# 02_POWER.net
KiCad netlist of a schematic drawn in Altium Designer
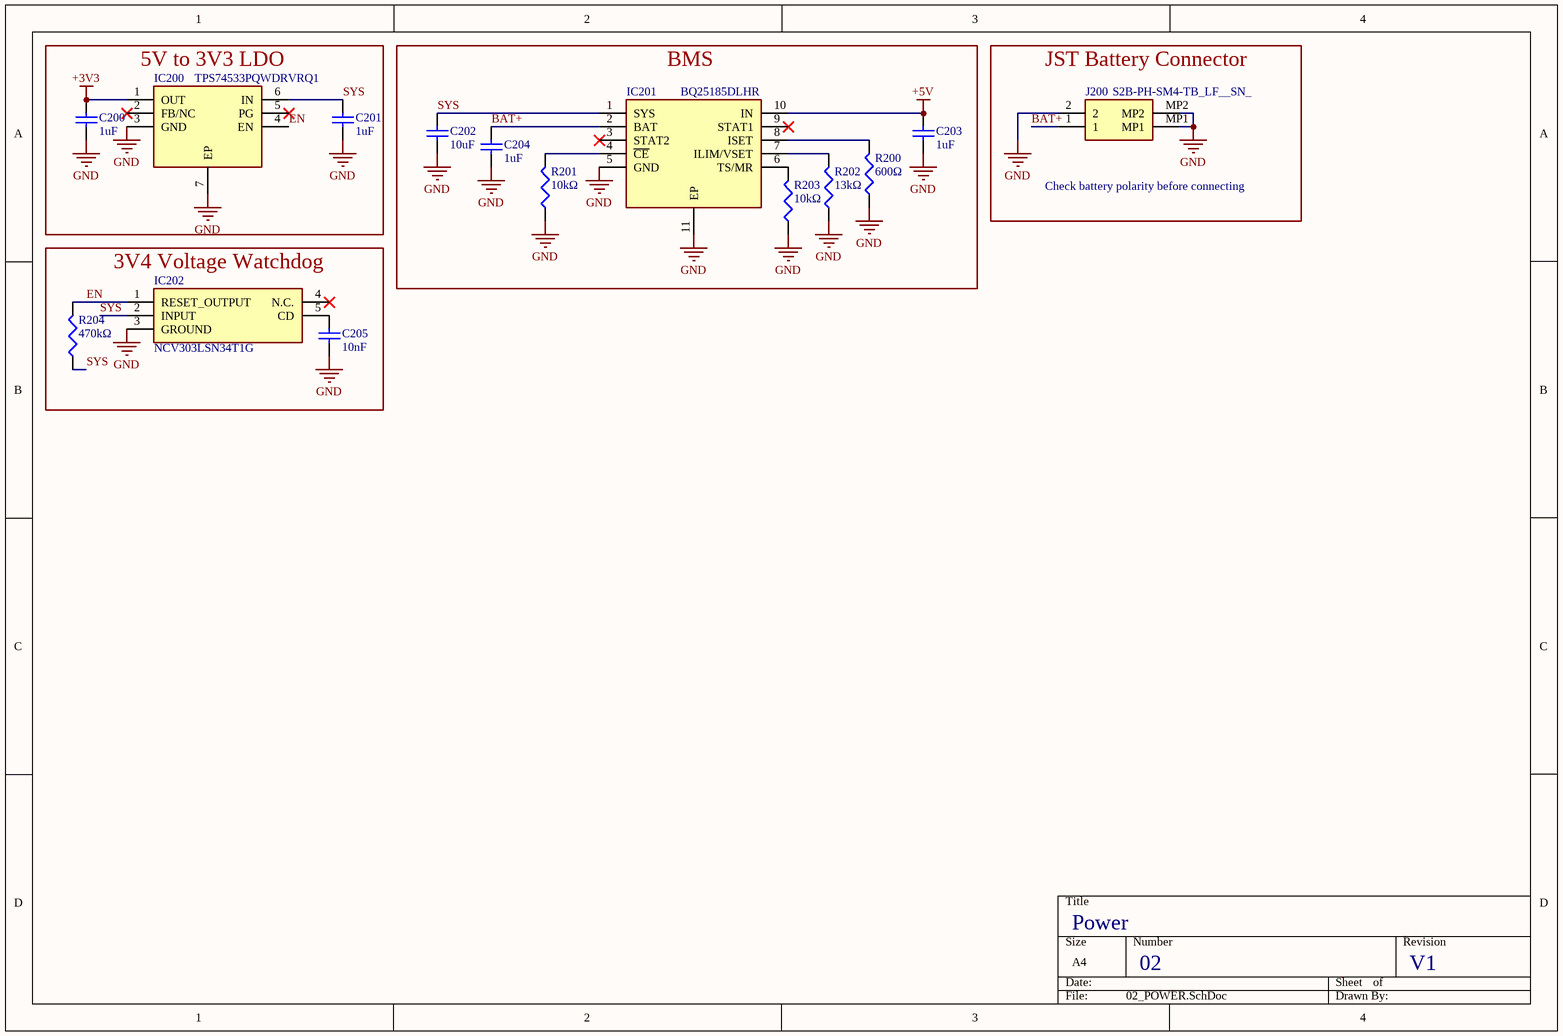
[diagram p0: 02_POWER.SchDoc]

(export (version "E")
  (design (tool "Eeschema 10.0.6"))
  (components
    (comp (ref "C200")
      (value "1uF")
      (footprint "CAPC1005X55X25LL05T10")
      (description "Chip Capacitor, 1 uF, +/- 10%, 6.3 V, 0402 (1005 Metric)")
      (fields (field (name "TOLERANCE") "10%") (field (name "Comment") "Capacitor 1 uF +/- 10% 6.3 V 0402"))
      (libsource (lib "CPRT Workspace") (part "CAP-NP-2"))
    )
    (comp (ref "C201")
      (value "1uF")
      (footprint "CAPC1005X55X25LL05T10")
      (description "Chip Capacitor, 1 uF, +/- 10%, 6.3 V, 0402 (1005 Metric)")
      (fields (field (name "TOLERANCE") "10%") (field (name "Comment") "Capacitor 1 uF +/- 10% 6.3 V 0402"))
      (libsource (lib "CPRT Workspace") (part "CAP-NP-2"))
    )
    (comp (ref "C202")
      (value "10uF")
      (footprint "CAPC1005X55X25LL05T10")
      (description "Chip Capacitor, 1 uF, +/- 10%, 6.3 V, 0402 (1005 Metric)")
      (fields (field (name "TOLERANCE") "10%") (field (name "Comment") "Capacitor 1 uF +/- 10% 6.3 V 0402"))
      (libsource (lib "CPRT Workspace") (part "CAP-NP-2"))
    )
    (comp (ref "C203")
      (value "1uF")
      (footprint "CAPC1005X55X25LL05T10")
      (description "Chip Capacitor, 1 uF, +/- 10%, 6.3 V, 0402 (1005 Metric)")
      (fields (field (name "TOLERANCE") "10%") (field (name "Comment") "Capacitor 1 uF +/- 10% 6.3 V 0402"))
      (libsource (lib "CPRT Workspace") (part "CAP-NP-2"))
    )
    (comp (ref "C204")
      (value "1uF")
      (footprint "CAPC1005X55X25LL05T10")
      (description "Chip Capacitor, 1 uF, +/- 10%, 6.3 V, 0402 (1005 Metric)")
      (fields (field (name "TOLERANCE") "10%") (field (name "Comment") "Capacitor 1 uF +/- 10% 6.3 V 0402"))
      (libsource (lib "CPRT Workspace") (part "CAP-NP-2"))
    )
    (comp (ref "C205")
      (value "10nF")
      (footprint "CAPC1005X55X25LL05T10")
      (description "Chip Capacitor, 1 uF, +/- 10%, 6.3 V, 0402 (1005 Metric)")
      (fields (field (name "TOLERANCE") "10%") (field (name "Comment") "Capacitor 1 uF +/- 10% 6.3 V 0402"))
      (libsource (lib "CPRT Workspace") (part "CAP-NP-2"))
    )
    (comp (ref "IC200")
      (value "TPS74533PQWDRVRQ1")
      (footprint "SON65P200X200X80-7N")
      (description "Integrated Circuit")
      (fields (field (name "MOUSER PART NUMBER") "595-PS74533PQWDRVRQ1"))
      (libsource (lib "Schlib1") (part "TPS74533PQWDRVRQ1"))
    )
    (comp (ref "IC201")
      (value "BQ25185DLHR")
      (footprint "SON40P220X200X80-11N")
      (description "Integrated Circuit")
      (fields (field (name "MOUSER PART NUMBER") "595-BQ25185DLHR"))
      (libsource (lib "Schlib1") (part "BQ25185DLHR"))
    )
    (comp (ref "IC202")
      (value "NCV303LSN34T1G")
      (footprint "SOT95P275X110-5N")
      (description "Integrated Circuit")
      (fields (field (name "MOUSER PART NUMBER") "863-NCV303LSN34T1G"))
      (libsource (lib "Schlib1") (part "NCV303LSN34T1G"))
    )
    (comp (ref "J200")
      (value "S2B-PH-SM4-TB_LF__SN_")
      (footprint "S2BPHSM4TBLFSN")
      (description "Connector")
      (fields (field (name "MANUFACTURER_PART_NUMBER") "S2B-PH-SM4-TB(LF)(SN)"))
      (libsource (lib "Schlib1") (part "S2B-PH-SM4-TB_LF__SN_"))
    )
    (comp (ref "R200")
      (value "600Ω")
      (footprint "RESC0402(1005)_L")
      (description "100R 0.063W 1% 0402 (1005 Metric)  SMD")
      (fields (field (name "TOLERANCE") "1%") (field (name "POWER") "63mW"))
      (libsource (lib "CPRT Workspace") (part "100R2F"))
    )
    (comp (ref "R201")
      (value "10kΩ")
      (footprint "RESC0402(1005)_L")
      (description "100R 0.063W 1% 0402 (1005 Metric)  SMD")
      (fields (field (name "TOLERANCE") "1%") (field (name "POWER") "63mW"))
      (libsource (lib "CPRT Workspace") (part "100R2F"))
    )
    (comp (ref "R202")
      (value "13kΩ")
      (footprint "RESC0402(1005)_L")
      (description "100R 0.063W 1% 0402 (1005 Metric)  SMD")
      (fields (field (name "TOLERANCE") "1%") (field (name "POWER") "63mW"))
      (libsource (lib "CPRT Workspace") (part "100R2F"))
    )
    (comp (ref "R203")
      (value "10kΩ")
      (footprint "RESC0402(1005)_L")
      (description "100R 0.063W 1% 0402 (1005 Metric)  SMD")
      (fields (field (name "TOLERANCE") "1%") (field (name "POWER") "63mW"))
      (libsource (lib "CPRT Workspace") (part "100R2F"))
    )
    (comp (ref "R204")
      (value "470kΩ")
      (footprint "RESC0402(1005)_L")
      (description "100R 0.063W 1% 0402 (1005 Metric)  SMD")
      (fields (field (name "TOLERANCE") "1%") (field (name "POWER") "63mW"))
      (libsource (lib "CPRT Workspace") (part "100R2F"))
    )
  )
  (nets
    (net (code "1") (name "+3V3") (class "Default")
      (node (ref "C200") (pin "2") (pinfunction "2_2") (pintype "passive"))
      (node (ref "IC200") (pin "1") (pinfunction "OUT_1") (pintype "passive"))
    )
    (net (code "2") (name "+5V") (class "Default")
      (node (ref "C203") (pin "2") (pinfunction "2_2") (pintype "passive"))
      (node (ref "IC201") (pin "10") (pinfunction "IN_10") (pintype "passive"))
    )
    (net (code "3") (name "/BAT+") (class "Default")
      (node (ref "C204") (pin "2") (pinfunction "2_2") (pintype "passive"))
      (node (ref "IC201") (pin "2") (pinfunction "BAT_2") (pintype "passive"))
      (node (ref "J200") (pin "1") (pinfunction "1_1") (pintype "passive"))
    )
    (net (code "4") (name "/EN") (class "Default")
      (node (ref "IC200") (pin "4") (pinfunction "EN_4") (pintype "passive"))
      (node (ref "IC202") (pin "1") (pinfunction "RESET_OUTPUT_1") (pintype "passive"))
      (node (ref "R204") (pin "2") (pinfunction "2_2") (pintype "passive"))
    )
    (net (code "5") (name "/SYS") (class "Default")
      (node (ref "C201") (pin "2") (pinfunction "2_2") (pintype "passive"))
      (node (ref "C202") (pin "2") (pinfunction "2_2") (pintype "passive"))
      (node (ref "IC200") (pin "6") (pinfunction "IN_6") (pintype "passive"))
      (node (ref "IC201") (pin "1") (pinfunction "SYS_1") (pintype "passive"))
      (node (ref "IC202") (pin "2") (pinfunction "INPUT_2") (pintype "passive"))
      (node (ref "R204") (pin "1") (pinfunction "1_1") (pintype "passive"))
    )
    (net (code "6") (name "GND") (class "Default")
      (node (ref "C200") (pin "1") (pinfunction "1_1") (pintype "passive"))
      (node (ref "C201") (pin "1") (pinfunction "1_1") (pintype "passive"))
      (node (ref "C202") (pin "1") (pinfunction "1_1") (pintype "passive"))
      (node (ref "C203") (pin "1") (pinfunction "1_1") (pintype "passive"))
      (node (ref "C204") (pin "1") (pinfunction "1_1") (pintype "passive"))
      (node (ref "C205") (pin "1") (pinfunction "1_1") (pintype "passive"))
      (node (ref "IC200") (pin "3") (pinfunction "GND_3") (pintype "passive"))
      (node (ref "IC200") (pin "7") (pinfunction "EP_7") (pintype "passive"))
      (node (ref "IC201") (pin "11") (pinfunction "EP_11") (pintype "passive"))
      (node (ref "IC201") (pin "5") (pinfunction "GND_5") (pintype "passive"))
      (node (ref "IC202") (pin "3") (pinfunction "GROUND_3") (pintype "passive"))
      (node (ref "J200") (pin "2") (pinfunction "2_2") (pintype "passive"))
      (node (ref "J200") (pin "MP1") (pinfunction "MP1_MP1") (pintype "passive"))
      (node (ref "J200") (pin "MP2") (pinfunction "MP2_MP2") (pintype "passive"))
      (node (ref "R200") (pin "1") (pinfunction "1_1") (pintype "passive"))
      (node (ref "R201") (pin "1") (pinfunction "1_1") (pintype "passive"))
      (node (ref "R202") (pin "1") (pinfunction "1_1") (pintype "passive"))
      (node (ref "R203") (pin "1") (pinfunction "1_1") (pintype "passive"))
    )
    (net (code "7") (name "Net-(IC201-ILIM{slash}VSET)") (class "Default")
      (node (ref "IC201") (pin "7") (pinfunction "ILIM/VSET_7") (pintype "passive"))
      (node (ref "R202") (pin "2") (pinfunction "2_2") (pintype "passive"))
    )
    (net (code "8") (name "Net-(IC201-ISET)") (class "Default")
      (node (ref "IC201") (pin "8") (pinfunction "ISET_8") (pintype "passive"))
      (node (ref "R200") (pin "2") (pinfunction "2_2") (pintype "passive"))
    )
    (net (code "9") (name "Net-(IC201-TS{slash}MR)") (class "Default")
      (node (ref "IC201") (pin "6") (pinfunction "TS/MR_6") (pintype "passive"))
      (node (ref "R203") (pin "2") (pinfunction "2_2") (pintype "passive"))
    )
    (net (code "10") (name "Net-(IC201-~{CE})") (class "Default")
      (node (ref "IC201") (pin "4") (pinfunction "~{CE}_4") (pintype "passive"))
      (node (ref "R201") (pin "2") (pinfunction "2_2") (pintype "passive"))
    )
    (net (code "11") (name "Net-(IC202-CD)") (class "Default")
      (node (ref "C205") (pin "2") (pinfunction "2_2") (pintype "passive"))
      (node (ref "IC202") (pin "5") (pinfunction "CD_5") (pintype "passive"))
    )
    (net (code "12") (name "unconnected-(IC200-FB{slash}NC-Pad2)") (class "Default")
      (node (ref "IC200") (pin "2") (pinfunction "FB/NC_2") (pintype "passive+no_connect"))
    )
    (net (code "13") (name "unconnected-(IC200-PG-Pad5)") (class "Default")
      (node (ref "IC200") (pin "5") (pinfunction "PG_5") (pintype "passive+no_connect"))
    )
    (net (code "14") (name "unconnected-(IC201-STAT1-Pad9)") (class "Default")
      (node (ref "IC201") (pin "9") (pinfunction "STAT1_9") (pintype "passive+no_connect"))
    )
    (net (code "15") (name "unconnected-(IC201-STAT2-Pad3)") (class "Default")
      (node (ref "IC201") (pin "3") (pinfunction "STAT2_3") (pintype "passive+no_connect"))
    )
    (net (code "16") (name "unconnected-(IC202-N.C.-Pad4)") (class "Default")
      (node (ref "IC202") (pin "4") (pinfunction "N.C._4") (pintype "passive+no_connect"))
    )
  )
)
